# EEZ_DIB_AUX_PS_r3B6.net
KiCad netlist of a schematic drawn in EAGLE
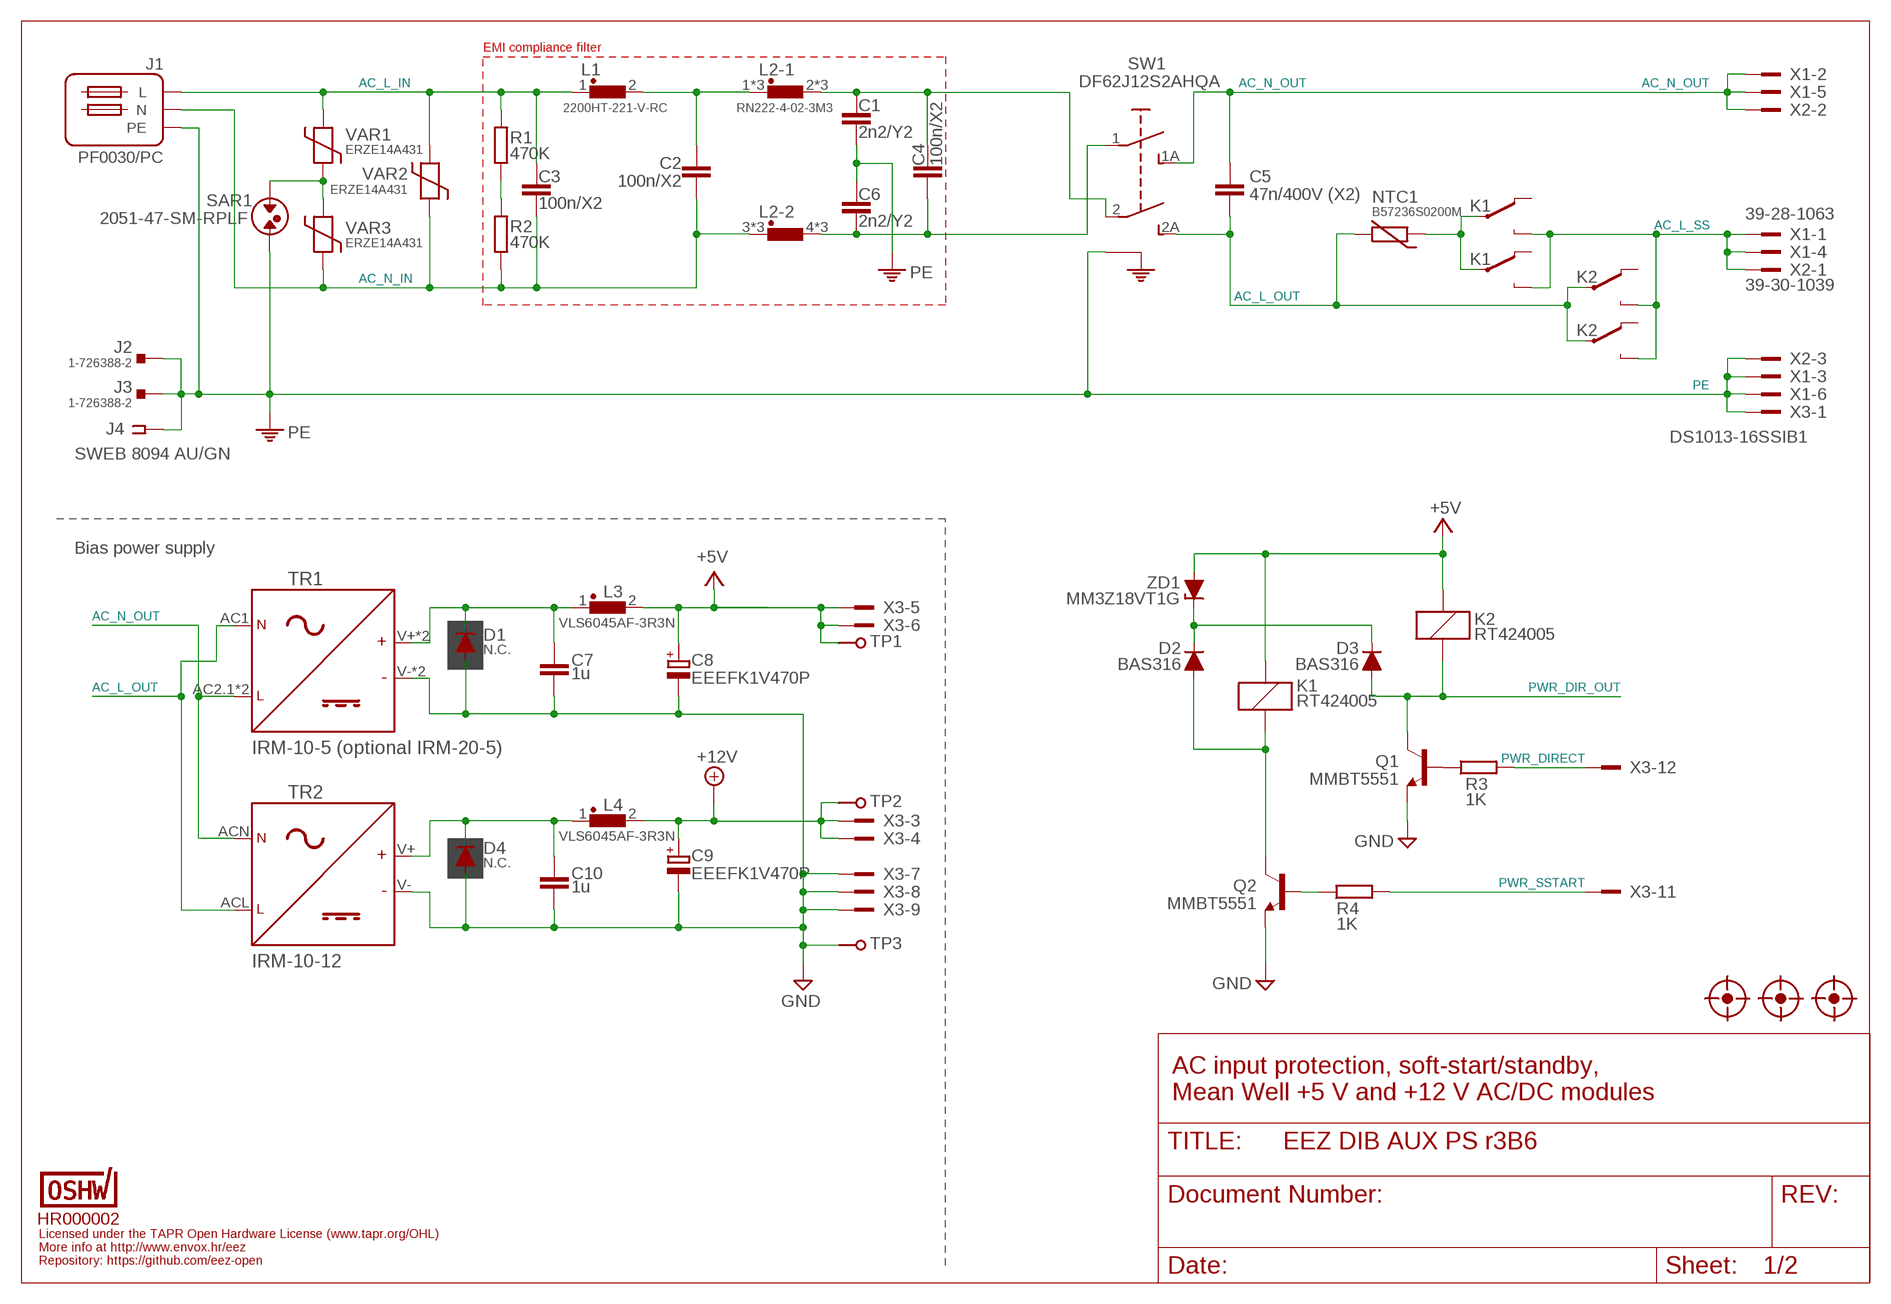
[diagram p0: schematic, sheet 1]
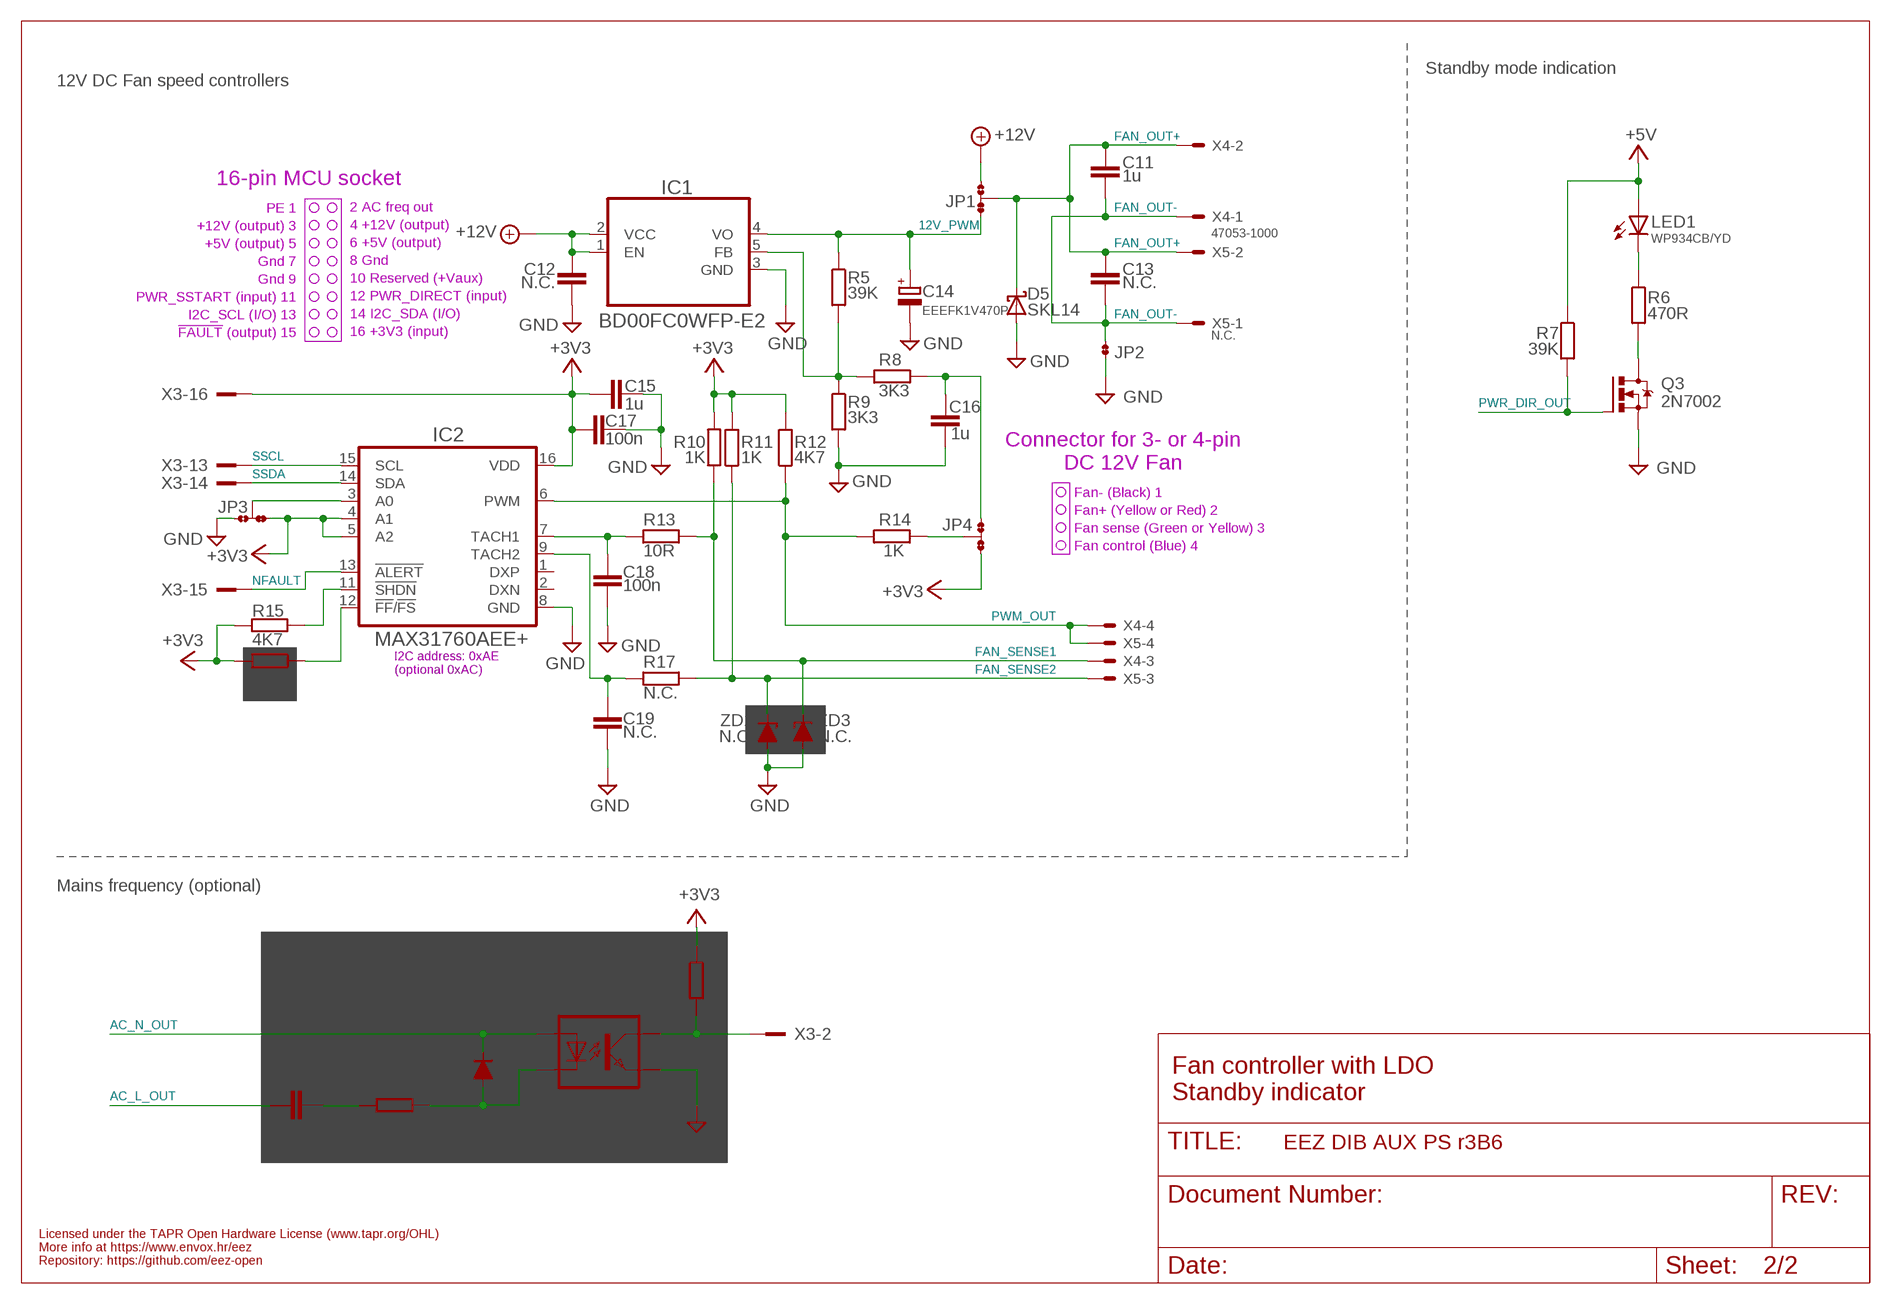
[diagram p1: schematic, sheet 2]

(export (version "E")
  (design (tool "Eeschema 10.0.6"))
  (components
    (comp (ref "C11")
      (value "1u")
      (footprint "eagle-import:C0805")
      (libsource (lib "eagle-import") (part "C-EUC0805"))
    )
    (comp (ref "C12")
      (value "N.C.")
      (footprint "eagle-import:C0805")
      (libsource (lib "eagle-import") (part "C-EUC0805"))
    )
    (comp (ref "C13")
      (value "N.C.")
      (footprint "eagle-import:C0805")
      (libsource (lib "eagle-import") (part "C-EUC0805"))
    )
    (comp (ref "C14")
      (value "EEEFK1V470P")
      (footprint "eagle-import:CAPAE660X610N")
      (libsource (lib "eagle-import") (part "ECAPPANASONIC_H"))
    )
    (comp (ref "C15")
      (value "1u")
      (footprint "eagle-import:C0805")
      (libsource (lib "eagle-import") (part "C-EUC0805"))
    )
    (comp (ref "C16")
      (value "1u")
      (footprint "eagle-import:C0805")
      (libsource (lib "eagle-import") (part "C-EUC0805"))
    )
    (comp (ref "C17")
      (value "100n")
      (footprint "eagle-import:C0603")
      (libsource (lib "eagle-import") (part "C-EUC0603"))
    )
    (comp (ref "C18")
      (value "100n")
      (footprint "eagle-import:C0603")
      (libsource (lib "eagle-import") (part "C-EUC0603"))
    )
    (comp (ref "C19")
      (value "N.C.")
      (footprint "eagle-import:C0603")
      (libsource (lib "eagle-import") (part "C-EUC0603"))
    )
    (comp (ref "C20")
      (value "N.C.")
      (footprint "eagle-import:C102-054X133")
      (libsource (lib "eagle-import") (part "C-EU102-054X133"))
    )
    (comp (ref "D5")
      (value "SKL14")
      (footprint "eagle-import:SOD123")
      (libsource (lib "eagle-import") (part "SCHOTTKYSOD123"))
    )
    (comp (ref "D6")
      (value "N.C.")
      (footprint "eagle-import:SOD323-R")
      (libsource (lib "eagle-import") (part "DIODESOD323R"))
    )
    (comp (ref "IC1")
      (value "BD00FC0WFP-E2")
      (footprint "eagle-import:TO-252-5")
      (libsource (lib "eagle-import") (part "BD00FC0W"))
    )
    (comp (ref "IC2")
      (value "MAX31760AEE+")
      (footprint "eagle-import:DBQ16")
      (libsource (lib "eagle-import") (part "MAX31760AEE+"))
    )
    (comp (ref "JP1")
      (value "JP3-CUT-0805-ROTATED")
      (footprint "eagle-import:JP3-0805-CUT2")
      (libsource (lib "eagle-import") (part "JP3-CUT-0805-ROTATED"))
    )
    (comp (ref "JP2")
      (value "JP2-NOCUT-0805")
      (footprint "eagle-import:JP2-0805-NOCUT")
      (libsource (lib "eagle-import") (part "JP2-NOCUT-0805"))
    )
    (comp (ref "JP3")
      (value "JP3-CUT-0805-ROTATED")
      (footprint "eagle-import:JP3-0805-CUT2")
      (libsource (lib "eagle-import") (part "JP3-CUT-0805-ROTATED"))
    )
    (comp (ref "JP4")
      (value "JP3-CUT-0805-ROTATED")
      (footprint "eagle-import:JP3-0805-CUT2")
      (libsource (lib "eagle-import") (part "JP3-CUT-0805-ROTATED"))
    )
    (comp (ref "LED1")
      (value "WP934CB/YD")
      (footprint "eagle-import:WP934CB_YD")
      (libsource (lib "eagle-import") (part "WP934CB/YD"))
    )
    (comp (ref "OK1")
      (value "N.C.")
      (footprint "eagle-import:SO4")
      (libsource (lib "eagle-import") (part "TLP291"))
    )
    (comp (ref "Q3")
      (value "2N7002")
      (footprint "eagle-import:SOT103P240X110-3N")
      (fields
        (field (name "MPN") "2N7002-7-F")
        (field (name "MPN_1") "2N7002-7-F")
        (field (name "OC_FARNELL") "1713823")
        (field (name "OC_NEWARK") "25R5679")
        (field (name "PACKAGE") "SOT-23-3")
        (field (name "SUPPLIER") "DIODES INC.")
      )
      (libsource (lib "eagle-import") (part "2N7002"))
    )
    (comp (ref "R5")
      (value "39K")
      (footprint "eagle-import:R0805")
      (libsource (lib "eagle-import") (part "R-EU_R0805"))
    )
    (comp (ref "R6")
      (value "470R")
      (footprint "eagle-import:R0805")
      (libsource (lib "eagle-import") (part "R-EU_R0805"))
    )
    (comp (ref "R7")
      (value "39K")
      (footprint "eagle-import:R0805")
      (libsource (lib "eagle-import") (part "R-EU_R0805"))
    )
    (comp (ref "R8")
      (value "3K3")
      (footprint "eagle-import:R0805")
      (libsource (lib "eagle-import") (part "R-EU_R0805"))
    )
    (comp (ref "R9")
      (value "3K3")
      (footprint "eagle-import:R0805")
      (libsource (lib "eagle-import") (part "R-EU_R0805"))
    )
    (comp (ref "R10")
      (value "1K")
      (footprint "eagle-import:R0805")
      (libsource (lib "eagle-import") (part "R-EU_R0805"))
    )
    (comp (ref "R11")
      (value "1K")
      (footprint "eagle-import:R0805")
      (libsource (lib "eagle-import") (part "R-EU_R0805"))
    )
    (comp (ref "R12")
      (value "4K7")
      (footprint "eagle-import:R0805")
      (libsource (lib "eagle-import") (part "R-EU_R0805"))
    )
    (comp (ref "R13")
      (value "10R")
      (footprint "eagle-import:R0805")
      (libsource (lib "eagle-import") (part "R-EU_R0805"))
    )
    (comp (ref "R14")
      (value "1K")
      (footprint "eagle-import:R0805")
      (libsource (lib "eagle-import") (part "R-EU_R0805"))
    )
    (comp (ref "R15")
      (value "4K7")
      (footprint "eagle-import:R0805")
      (libsource (lib "eagle-import") (part "R-EU_R0805"))
    )
    (comp (ref "R16")
      (value "N.C.")
      (footprint "eagle-import:R0805")
      (libsource (lib "eagle-import") (part "R-EU_R0805"))
    )
    (comp (ref "R17")
      (value "N.C.")
      (footprint "eagle-import:R0805")
      (libsource (lib "eagle-import") (part "R-EU_R0805"))
    )
    (comp (ref "R18")
      (value "N.C.")
      (footprint "eagle-import:R0805")
      (libsource (lib "eagle-import") (part "R-EU_R0805"))
    )
    (comp (ref "R19")
      (value "N.C.")
      (footprint "eagle-import:R0805")
      (libsource (lib "eagle-import") (part "R-EU_R0805"))
    )
    (comp (ref "X3")
      (value "DS1013-16SSIB1")
      (footprint "eagle-import:IDC-16PIN")
      (libsource (lib "eagle-import") (part "IDC-16PIN"))
    )
    (comp (ref "X4")
      (value "47053-1000")
      (footprint "eagle-import:47053-1000")
      (libsource (lib "eagle-import") (part "47053-1000"))
    )
    (comp (ref "X5")
      (value "N.C.")
      (footprint "eagle-import:47053-1000")
      (libsource (lib "eagle-import") (part "47053-1000"))
    )
    (comp (ref "ZD2")
      (value "N.C.")
      (footprint "eagle-import:SOD123")
      (libsource (lib "eagle-import") (part "ZENER-DIODESOD123"))
    )
    (comp (ref "ZD3")
      (value "N.C.")
      (footprint "eagle-import:SOD123")
      (libsource (lib "eagle-import") (part "ZENER-DIODESOD123"))
    )
    (comp (ref "C1")
      (value "2n2/Y2")
      (footprint "eagle-import:C075-042X103")
      (libsource (lib "eagle-import") (part "C-EU075-042X103"))
    )
    (comp (ref "C2")
      (value "100n/X2")
      (footprint "eagle-import:C150-054X183")
      (libsource (lib "eagle-import") (part "C-EU150-054X183"))
    )
    (comp (ref "C3")
      (value "100n/X2")
      (footprint "eagle-import:C150-054X183")
      (libsource (lib "eagle-import") (part "C-EU150-054X183"))
    )
    (comp (ref "C4")
      (value "100n/X2")
      (footprint "eagle-import:C150-054X183")
      (libsource (lib "eagle-import") (part "C-EU150-054X183"))
    )
    (comp (ref "C5")
      (value "47n/400V (X2)")
      (footprint "eagle-import:C102-054X133")
      (libsource (lib "eagle-import") (part "C-EU102-054X133"))
    )
    (comp (ref "C6")
      (value "2n2/Y2")
      (footprint "eagle-import:C075-042X103")
      (libsource (lib "eagle-import") (part "C-EU075-042X103"))
    )
    (comp (ref "C7")
      (value "1u")
      (footprint "eagle-import:C0805")
      (libsource (lib "eagle-import") (part "C-EUC0805"))
    )
    (comp (ref "C8")
      (value "EEEFK1V470P")
      (footprint "eagle-import:CAPAE660X610N")
      (libsource (lib "eagle-import") (part "ECAPPANASONIC_H"))
    )
    (comp (ref "C9")
      (value "EEEFK1V470P")
      (footprint "eagle-import:CAPAE660X610N")
      (libsource (lib "eagle-import") (part "ECAPPANASONIC_H"))
    )
    (comp (ref "C10")
      (value "1u")
      (footprint "eagle-import:C0805")
      (libsource (lib "eagle-import") (part "C-EUC0805"))
    )
    (comp (ref "D1")
      (value "N.C.")
      (footprint "eagle-import:DO214AA")
      (libsource (lib "eagle-import") (part "MyLib6_DIODEDO214AA"))
    )
    (comp (ref "D2")
      (value "BAS316")
      (footprint "eagle-import:SOD323-R")
      (libsource (lib "eagle-import") (part "DIODESOD323R"))
    )
    (comp (ref "D3")
      (value "BAS316")
      (footprint "eagle-import:SOD323-R")
      (libsource (lib "eagle-import") (part "DIODESOD323R"))
    )
    (comp (ref "D4")
      (value "N.C.")
      (footprint "eagle-import:DO214AA")
      (libsource (lib "eagle-import") (part "MyLib6_DIODEDO214AA"))
    )
    (comp (ref "FM1")
      (value "FIDUCIAL")
      (footprint "eagle-import:FIDUCIAL")
      (libsource (lib "eagle-import") (part "FIDUCIAL"))
    )
    (comp (ref "FM2")
      (value "FIDUCIAL")
      (footprint "eagle-import:FIDUCIAL")
      (libsource (lib "eagle-import") (part "FIDUCIAL"))
    )
    (comp (ref "FM3")
      (value "FIDUCIAL")
      (footprint "eagle-import:FIDUCIAL")
      (libsource (lib "eagle-import") (part "FIDUCIAL"))
    )
    (comp (ref "J1")
      (value "PF0030/PC")
      (footprint "eagle-import:PF0030_PC")
      (libsource (lib "eagle-import") (part "PF0030/PC"))
    )
    (comp (ref "J2")
      (value "1-726388-2")
      (footprint "eagle-import:PCB_TAB-4.8MM")
      (libsource (lib "eagle-import") (part "PCB_TAB4.8MM"))
    )
    (comp (ref "J3")
      (value "1-726388-2")
      (footprint "eagle-import:PCB_TAB-4.8MM")
      (libsource (lib "eagle-import") (part "PCB_TAB4.8MM"))
    )
    (comp (ref "J4")
      (value "SWEB 8094 AU/GN")
      (footprint "eagle-import:S16N-PC")
      (libsource (lib "eagle-import") (part "BINDING_POSTCLIFF"))
    )
    (comp (ref "K1")
      (value "RT424005")
      (footprint "eagle-import:RT-C_016A5_ROUND")
      (libsource (lib "eagle-import") (part "RELAY_RT314012-2"))
    )
    (comp (ref "K2")
      (value "RT424005")
      (footprint "eagle-import:RT-C_016A5_ROUND")
      (libsource (lib "eagle-import") (part "RELAY_RT314012-2"))
    )
    (comp (ref "L1")
      (value "2200HT-221-V-RC")
      (footprint "eagle-import:BOURNS_2200")
      (libsource (lib "eagle-import") (part "BOURNS_2200"))
    )
    (comp (ref "L2")
      (value "RN222-4-02-3M3")
      (footprint "eagle-import:BOURNS_7100_COMBO")
      (libsource (lib "eagle-import") (part "BOURNS_7100-COMBO"))
    )
    (comp (ref "L3")
      (value "VLS6045AF-3R3N")
      (footprint "eagle-import:COILCRAFT_HPI0630")
      (libsource (lib "eagle-import") (part "COILCRAFT_HPI0630"))
    )
    (comp (ref "L4")
      (value "VLS6045AF-3R3N")
      (footprint "eagle-import:COILCRAFT_HPI0630")
      (libsource (lib "eagle-import") (part "COILCRAFT_HPI0630"))
    )
    (comp (ref "LABEL1")
      (value "HR000002")
      (footprint "eagle-import:CERT-SMALL-SILK")
      (libsource (lib "eagle-import") (part "OSHWA-CERT-SMALL"))
    )
    (comp (ref "NTC1")
      (value "B57236S0200M")
      (footprint "eagle-import:NTC_11.5X6_RM5")
      (libsource (lib "eagle-import") (part "NTC11.5X6"))
    )
    (comp (ref "Q1")
      (value "MMBT5551")
      (footprint "eagle-import:SOT23-BEC")
      (libsource (lib "eagle-import") (part "-NPN-SOT23-BECMMBT5551LT1"))
    )
    (comp (ref "Q2")
      (value "MMBT5551")
      (footprint "eagle-import:SOT23-BEC")
      (libsource (lib "eagle-import") (part "-NPN-SOT23-BECMMBT5551LT1"))
    )
    (comp (ref "R1")
      (value "470K")
      (footprint "eagle-import:R1206")
      (libsource (lib "eagle-import") (part "R-EU_R1206"))
    )
    (comp (ref "R2")
      (value "470K")
      (footprint "eagle-import:R1206")
      (libsource (lib "eagle-import") (part "R-EU_R1206"))
    )
    (comp (ref "R3")
      (value "1K")
      (footprint "eagle-import:R0805")
      (libsource (lib "eagle-import") (part "R-EU_R0805"))
    )
    (comp (ref "R4")
      (value "1K")
      (footprint "eagle-import:R0805")
      (libsource (lib "eagle-import") (part "R-EU_R0805"))
    )
    (comp (ref "SAR1")
      (value "2051-47-SM-RPLF")
      (footprint "eagle-import:SAR_4.5MM")
      (libsource (lib "eagle-import") (part "SAR-SG"))
    )
    (comp (ref "SW1")
      (value "DF62J12S2AHQA")
      (footprint "eagle-import:DF62J12S2")
      (libsource (lib "eagle-import") (part "DF62J12S2AHQA"))
    )
    (comp (ref "TP1")
      (value "PCB_TEST_TABSHIELD")
      (footprint "eagle-import:PCB_SHIELD_TAB")
      (libsource (lib "eagle-import") (part "PCB_TEST_TABSHIELD"))
    )
    (comp (ref "TP2")
      (value "PCB_TEST_TABSHIELD")
      (footprint "eagle-import:PCB_SHIELD_TAB")
      (libsource (lib "eagle-import") (part "PCB_TEST_TABSHIELD"))
    )
    (comp (ref "TP3")
      (value "PCB_TEST_TABSHIELD")
      (footprint "eagle-import:PCB_SHIELD_TAB")
      (libsource (lib "eagle-import") (part "PCB_TEST_TABSHIELD"))
    )
    (comp (ref "TR1")
      (value "IRM-10-5 (optional IRM-20-5)")
      (footprint "eagle-import:IRM-10_20_COMBO")
      (libsource (lib "eagle-import") (part "AC_DC_ADAPTERIRM10/20"))
    )
    (comp (ref "TR2")
      (value "IRM-10-12")
      (footprint "eagle-import:IRM-10")
      (libsource (lib "eagle-import") (part "AC_DC_ADAPTERIRM10"))
    )
    (comp (ref "VAR1")
      (value "ERZE14A431")
      (footprint "eagle-import:VARISTOR_16MM")
      (libsource (lib "eagle-import") (part "VARISTOR-16"))
    )
    (comp (ref "VAR2")
      (value "ERZE14A431")
      (footprint "eagle-import:VARISTOR_16MM")
      (libsource (lib "eagle-import") (part "VARISTOR-16"))
    )
    (comp (ref "VAR3")
      (value "ERZE14A431")
      (footprint "eagle-import:VARISTOR_16MM")
      (libsource (lib "eagle-import") (part "VARISTOR-16"))
    )
    (comp (ref "X1")
      (value "39-28-1063")
      (footprint "eagle-import:MINIFIT_5566-06A_CRE")
      (libsource (lib "eagle-import") (part "MINIFIT_5566-06A-CRE"))
    )
    (comp (ref "X2")
      (value "39-30-1039")
      (footprint "eagle-import:MINIFIT_39301039_CRE")
      (libsource (lib "eagle-import") (part "MINIFIT_39301039-CREEPAGE"))
    )
    (comp (ref "ZD1")
      (value "MM3Z18VT1G")
      (footprint "eagle-import:SOD323-R")
      (libsource (lib "eagle-import") (part "ZENER-DIODESOD323R"))
    )
  )
  (nets
    (net (code "1") (name "+3V3") (class "Default")
      (node (ref "C15") (pin "2") (pinfunction "2_2") (pintype "passive"))
      (node (ref "C17") (pin "2") (pinfunction "2_2") (pintype "passive"))
      (node (ref "IC2") (pin "16") (pinfunction "VDD_16") (pintype "power_in"))
      (node (ref "IC2") (pin "4") (pinfunction "A1_4") (pintype "input"))
      (node (ref "IC2") (pin "5") (pinfunction "A2_5") (pintype "input"))
      (node (ref "JP3") (pin "NC") (pinfunction "NC_NC") (pintype "passive"))
      (node (ref "JP4") (pin "NO") (pinfunction "NO_NO") (pintype "passive"))
      (node (ref "R10") (pin "2") (pinfunction "2_2") (pintype "passive"))
      (node (ref "R11") (pin "2") (pinfunction "2_2") (pintype "passive"))
      (node (ref "R12") (pin "2") (pinfunction "2_2") (pintype "passive"))
      (node (ref "R15") (pin "2") (pinfunction "2_2") (pintype "passive"))
      (node (ref "R16") (pin "2") (pinfunction "2_2") (pintype "passive"))
      (node (ref "R18") (pin "1") (pinfunction "1_1") (pintype "passive"))
      (node (ref "X3") (pin "16") (pinfunction "1_16") (pintype "passive"))
    )
    (net (code "2") (name "+5V") (class "Default")
      (node (ref "C8") (pin "1") (pinfunction "+_1") (pintype "passive"))
      (node (ref "K1") (pin "A2") (pinfunction "C1_A2") (pintype "passive"))
      (node (ref "K2") (pin "A1") (pinfunction "C2_A1") (pintype "passive"))
      (node (ref "L3") (pin "2") (pinfunction "2_2") (pintype "passive"))
      (node (ref "LED1") (pin "A") (pinfunction "A_A") (pintype "passive"))
      (node (ref "R7") (pin "1") (pinfunction "1_1") (pintype "passive"))
      (node (ref "TP1") (pin "1") (pinfunction "P$1_1") (pintype "bidirectional"))
      (node (ref "X3") (pin "5") (pinfunction "1_5") (pintype "passive"))
      (node (ref "X3") (pin "6") (pinfunction "1_6") (pintype "passive"))
      (node (ref "ZD1") (pin "A") (pinfunction "A_A") (pintype "passive"))
    )
    (net (code "3") (name "+12V") (class "Default")
      (node (ref "C12") (pin "1") (pinfunction "1_1") (pintype "passive"))
      (node (ref "C9") (pin "1") (pinfunction "+_1") (pintype "passive"))
      (node (ref "IC1") (pin "1") (pinfunction "EN_1") (pintype "passive"))
      (node (ref "IC1") (pin "2") (pinfunction "VCC_2") (pintype "passive"))
      (node (ref "JP1") (pin "NO") (pinfunction "NO_NO") (pintype "passive"))
      (node (ref "L4") (pin "2") (pinfunction "2_2") (pintype "passive"))
      (node (ref "TP2") (pin "1") (pinfunction "P$1_1") (pintype "bidirectional"))
      (node (ref "X3") (pin "3") (pinfunction "1_3") (pintype "passive"))
      (node (ref "X3") (pin "4") (pinfunction "1_4") (pintype "passive"))
    )
    (net (code "4") (name "12V_PWM") (class "Default")
      (node (ref "C14") (pin "1") (pinfunction "+_1") (pintype "passive"))
      (node (ref "IC1") (pin "4") (pinfunction "VO_4") (pintype "output"))
      (node (ref "JP1") (pin "NC") (pinfunction "NC_NC") (pintype "passive"))
      (node (ref "R5") (pin "1") (pinfunction "1_1") (pintype "passive"))
    )
    (net (code "5") (name "AC_L_IN") (class "Default")
      (node (ref "C3") (pin "1") (pinfunction "1_1") (pintype "passive"))
      (node (ref "J1") (pin "L") (pinfunction "L_L") (pintype "bidirectional"))
      (node (ref "L1") (pin "1") (pinfunction "1_1") (pintype "passive"))
      (node (ref "R1") (pin "2") (pinfunction "2_2") (pintype "passive"))
      (node (ref "VAR1") (pin "2") (pinfunction "P$2_2") (pintype "bidirectional"))
      (node (ref "VAR2") (pin "1") (pinfunction "P$1_1") (pintype "bidirectional"))
    )
    (net (code "6") (name "AC_L_OUT") (class "Default")
      (node (ref "C20") (pin "1") (pinfunction "1_1") (pintype "passive"))
      (node (ref "C5") (pin "2") (pinfunction "2_2") (pintype "passive"))
      (node (ref "K2") (pin "11A") (pinfunction "P_11A") (pintype "passive"))
      (node (ref "K2") (pin "11B") (pinfunction "P_11B") (pintype "passive"))
      (node (ref "NTC1") (pin "1") (pinfunction "P$1_1") (pintype "bidirectional"))
      (node (ref "SW1") (pin "2A") (pinfunction "S1_2A") (pintype "passive"))
      (node (ref "TR1") (pin "AC1") (pinfunction "AC/N_AC1") (pintype "input"))
      (node (ref "TR2") (pin "ACL") (pinfunction "AC/L_ACL") (pintype "input"))
    )
    (net (code "7") (name "AC_L_SS") (class "Default")
      (node (ref "K1") (pin "14A") (pinfunction "O_14A") (pintype "passive"))
      (node (ref "K1") (pin "14B") (pinfunction "O_14B") (pintype "passive"))
      (node (ref "K2") (pin "14A") (pinfunction "O_14A") (pintype "passive"))
      (node (ref "K2") (pin "14B") (pinfunction "O_14B") (pintype "passive"))
      (node (ref "X1") (pin "1") (pinfunction "1_1") (pintype "passive"))
      (node (ref "X1") (pin "4") (pinfunction "1_4") (pintype "passive"))
      (node (ref "X2") (pin "1") (pinfunction "1_1") (pintype "passive"))
    )
    (net (code "8") (name "AC_N_IN") (class "Default")
      (node (ref "C2") (pin "2") (pinfunction "2_2") (pintype "passive"))
      (node (ref "C3") (pin "2") (pinfunction "2_2") (pintype "passive"))
      (node (ref "J1") (pin "N") (pinfunction "N_N") (pintype "bidirectional"))
      (node (ref "L2") (pin "3") (pinfunction "1_3") (pintype "passive"))
      (node (ref "L2") (pin "3A") (pinfunction "1_3A") (pintype "passive"))
      (node (ref "L2") (pin "3B") (pinfunction "1_3B") (pintype "passive"))
      (node (ref "R2") (pin "1") (pinfunction "1_1") (pintype "passive"))
      (node (ref "VAR2") (pin "2") (pinfunction "P$2_2") (pintype "bidirectional"))
      (node (ref "VAR3") (pin "1") (pinfunction "P$1_1") (pintype "bidirectional"))
    )
    (net (code "9") (name "AC_N_OUT") (class "Default")
      (node (ref "C5") (pin "1") (pinfunction "1_1") (pintype "passive"))
      (node (ref "D6") (pin "C") (pinfunction "C_C") (pintype "passive"))
      (node (ref "OK1") (pin "1") (pinfunction "A_1") (pintype "passive"))
      (node (ref "SW1") (pin "1A") (pinfunction "S_1A") (pintype "passive"))
      (node (ref "TR1") (pin "AC2.1") (pinfunction "AC/L_AC2.1") (pintype "input"))
      (node (ref "TR1") (pin "AC2.2") (pinfunction "AC/L_AC2.2") (pintype "input"))
      (node (ref "TR2") (pin "ACN") (pinfunction "AC/N_ACN") (pintype "input"))
      (node (ref "X1") (pin "2") (pinfunction "1_2") (pintype "passive"))
      (node (ref "X1") (pin "5") (pinfunction "1_5") (pintype "passive"))
      (node (ref "X2") (pin "2") (pinfunction "1_2") (pintype "passive"))
    )
    (net (code "10") (name "FAN_OUT+") (class "Default")
      (node (ref "C11") (pin "1") (pinfunction "1_1") (pintype "passive"))
      (node (ref "C13") (pin "1") (pinfunction "1_1") (pintype "passive"))
      (node (ref "D5") (pin "C") (pinfunction "C_C") (pintype "passive"))
      (node (ref "JP1") (pin "COM") (pinfunction "COM_COM") (pintype "passive"))
      (node (ref "X4") (pin "2") (pinfunction "S_2") (pintype "passive"))
      (node (ref "X5") (pin "2") (pinfunction "S_2") (pintype "passive"))
    )
    (net (code "11") (name "FAN_OUT-") (class "Default")
      (node (ref "C11") (pin "2") (pinfunction "2_2") (pintype "passive"))
      (node (ref "C13") (pin "2") (pinfunction "2_2") (pintype "passive"))
      (node (ref "JP2") (pin "2") (pinfunction "2_2") (pintype "passive"))
      (node (ref "X4") (pin "1") (pinfunction "S_1") (pintype "passive"))
      (node (ref "X5") (pin "1") (pinfunction "S_1") (pintype "passive"))
    )
    (net (code "12") (name "FAN_SENSE1") (class "Default")
      (node (ref "R10") (pin "1") (pinfunction "1_1") (pintype "passive"))
      (node (ref "R13") (pin "2") (pinfunction "2_2") (pintype "passive"))
      (node (ref "X4") (pin "3") (pinfunction "S_3") (pintype "passive"))
      (node (ref "ZD3") (pin "C") (pinfunction "C_C") (pintype "passive"))
    )
    (net (code "13") (name "FAN_SENSE2") (class "Default")
      (node (ref "R11") (pin "1") (pinfunction "1_1") (pintype "passive"))
      (node (ref "R17") (pin "2") (pinfunction "2_2") (pintype "passive"))
      (node (ref "X5") (pin "3") (pinfunction "S_3") (pintype "passive"))
      (node (ref "ZD2") (pin "C") (pinfunction "C_C") (pintype "passive"))
    )
    (net (code "14") (name "GND") (class "Default")
      (node (ref "C10") (pin "2") (pinfunction "2_2") (pintype "passive"))
      (node (ref "C12") (pin "2") (pinfunction "2_2") (pintype "passive"))
      (node (ref "C14") (pin "2") (pinfunction "-_2") (pintype "passive"))
      (node (ref "C15") (pin "1") (pinfunction "1_1") (pintype "passive"))
      (node (ref "C16") (pin "2") (pinfunction "2_2") (pintype "passive"))
      (node (ref "C17") (pin "1") (pinfunction "1_1") (pintype "passive"))
      (node (ref "C18") (pin "2") (pinfunction "2_2") (pintype "passive"))
      (node (ref "C19") (pin "2") (pinfunction "2_2") (pintype "passive"))
      (node (ref "C7") (pin "2") (pinfunction "2_2") (pintype "passive"))
      (node (ref "C8") (pin "2") (pinfunction "-_2") (pintype "passive"))
      (node (ref "C9") (pin "2") (pinfunction "-_2") (pintype "passive"))
      (node (ref "D1") (pin "A") (pinfunction "A_A") (pintype "passive"))
      (node (ref "D4") (pin "A") (pinfunction "A_A") (pintype "passive"))
      (node (ref "D5") (pin "A") (pinfunction "A_A") (pintype "passive"))
      (node (ref "IC1") (pin "3") (pinfunction "GND_3") (pintype "passive"))
      (node (ref "IC2") (pin "8") (pinfunction "GND_8") (pintype "power_in"))
      (node (ref "JP2") (pin "1") (pinfunction "1_1") (pintype "passive"))
      (node (ref "JP3") (pin "NO") (pinfunction "NO_NO") (pintype "passive"))
      (node (ref "OK1") (pin "3") (pinfunction "EMIT_3") (pintype "passive"))
      (node (ref "Q1") (pin "E") (pinfunction "E_E") (pintype "passive"))
      (node (ref "Q2") (pin "E") (pinfunction "E_E") (pintype "passive"))
      (node (ref "Q3") (pin "2") (pinfunction "S_2") (pintype "passive"))
      (node (ref "R9") (pin "2") (pinfunction "2_2") (pintype "passive"))
      (node (ref "TP3") (pin "1") (pinfunction "P$1_1") (pintype "bidirectional"))
      (node (ref "TR1") (pin "V-") (pinfunction "-_V-") (pintype "passive"))
      (node (ref "TR1") (pin "V-1") (pinfunction "-_V-1") (pintype "passive"))
      (node (ref "TR2") (pin "V-") (pinfunction "-_V-") (pintype "passive"))
      (node (ref "X3") (pin "7") (pinfunction "1_7") (pintype "passive"))
      (node (ref "X3") (pin "8") (pinfunction "1_8") (pintype "passive"))
      (node (ref "X3") (pin "9") (pinfunction "1_9") (pintype "passive"))
      (node (ref "ZD2") (pin "A") (pinfunction "A_A") (pintype "passive"))
      (node (ref "ZD3") (pin "A") (pinfunction "A_A") (pintype "passive"))
    )
    (net (code "15") (name "NFAULT") (class "Default")
      (node (ref "IC2") (pin "13") (pinfunction "~{ALERT}_13") (pintype "output"))
      (node (ref "X3") (pin "15") (pinfunction "1_15") (pintype "passive"))
    )
    (net (code "16") (name "Net-(C2-Pad1)") (class "Default")
      (node (ref "C2") (pin "1") (pinfunction "1_1") (pintype "passive"))
      (node (ref "L1") (pin "2") (pinfunction "2_2") (pintype "passive"))
      (node (ref "L2") (pin "1") (pinfunction "1_1") (pintype "passive"))
      (node (ref "L2") (pin "1A") (pinfunction "1_1A") (pintype "passive"))
      (node (ref "L2") (pin "1B") (pinfunction "1_1B") (pintype "passive"))
    )
    (net (code "17") (name "Net-(C7-Pad1)") (class "Default")
      (node (ref "C7") (pin "1") (pinfunction "1_1") (pintype "passive"))
      (node (ref "D1") (pin "C") (pinfunction "C_C") (pintype "passive"))
      (node (ref "L3") (pin "1") (pinfunction "1_1") (pintype "passive"))
      (node (ref "TR1") (pin "V+") (pinfunction "+_V+") (pintype "passive"))
      (node (ref "TR1") (pin "V+1") (pinfunction "+_V+1") (pintype "passive"))
    )
    (net (code "18") (name "Net-(C16-Pad1)") (class "Default")
      (node (ref "C16") (pin "1") (pinfunction "1_1") (pintype "passive"))
      (node (ref "JP4") (pin "NC") (pinfunction "NC_NC") (pintype "passive"))
      (node (ref "R8") (pin "2") (pinfunction "2_2") (pintype "passive"))
    )
    (net (code "19") (name "Net-(C20-Pad2)") (class "Default")
      (node (ref "C20") (pin "2") (pinfunction "2_2") (pintype "passive"))
      (node (ref "R19") (pin "1") (pinfunction "1_1") (pintype "passive"))
    )
    (net (code "20") (name "Net-(D2-PadC)") (class "Default")
      (node (ref "D2") (pin "C") (pinfunction "C_C") (pintype "passive"))
      (node (ref "D3") (pin "C") (pinfunction "C_C") (pintype "passive"))
      (node (ref "ZD1") (pin "C") (pinfunction "C_C") (pintype "passive"))
    )
    (net (code "21") (name "Net-(IC1-FB)") (class "Default")
      (node (ref "IC1") (pin "5") (pinfunction "FB_5") (pintype "passive"))
      (node (ref "R5") (pin "2") (pinfunction "2_2") (pintype "passive"))
      (node (ref "R8") (pin "1") (pinfunction "1_1") (pintype "passive"))
      (node (ref "R9") (pin "1") (pinfunction "1_1") (pintype "passive"))
    )
    (net (code "22") (name "Net-(IC2-A0)") (class "Default")
      (node (ref "IC2") (pin "3") (pinfunction "A0_3") (pintype "input"))
      (node (ref "JP3") (pin "COM") (pinfunction "COM_COM") (pintype "passive"))
    )
    (net (code "23") (name "Net-(IC2-TACH1)") (class "Default")
      (node (ref "C18") (pin "1") (pinfunction "1_1") (pintype "passive"))
      (node (ref "IC2") (pin "7") (pinfunction "TACH1_7") (pintype "input"))
      (node (ref "R13") (pin "1") (pinfunction "1_1") (pintype "passive"))
    )
    (net (code "24") (name "Net-(IC2-TACH2)") (class "Default")
      (node (ref "C19") (pin "1") (pinfunction "1_1") (pintype "passive"))
      (node (ref "IC2") (pin "9") (pinfunction "TACH2_9") (pintype "input"))
      (node (ref "R17") (pin "1") (pinfunction "1_1") (pintype "passive"))
    )
    (net (code "25") (name "Net-(IC2-~{FF}{slash}~{FS})") (class "Default")
      (node (ref "IC2") (pin "12") (pinfunction "~{FF}/~{FS}_12") (pintype "bidirectional"))
      (node (ref "R16") (pin "1") (pinfunction "1_1") (pintype "passive"))
    )
    (net (code "26") (name "Net-(IC2-~{SHDN})") (class "Default")
      (node (ref "IC2") (pin "11") (pinfunction "~{SHDN}_11") (pintype "output"))
      (node (ref "R15") (pin "1") (pinfunction "1_1") (pintype "passive"))
    )
    (net (code "27") (name "Net-(JP4-PadCOM)") (class "Default")
      (node (ref "JP4") (pin "COM") (pinfunction "COM_COM") (pintype "passive"))
      (node (ref "R14") (pin "1") (pinfunction "1_1") (pintype "passive"))
    )
    (net (code "28") (name "Net-(K1A-P)") (class "Default")
      (node (ref "K1") (pin "11A") (pinfunction "P_11A") (pintype "passive"))
      (node (ref "K1") (pin "11B") (pinfunction "P_11B") (pintype "passive"))
      (node (ref "NTC1") (pin "2") (pinfunction "P$2_2") (pintype "bidirectional"))
    )
    (net (code "29") (name "Net-(K1C-C2)") (class "Default")
      (node (ref "D2") (pin "A") (pinfunction "A_A") (pintype "passive"))
      (node (ref "K1") (pin "A1") (pinfunction "C2_A1") (pintype "passive"))
      (node (ref "Q2") (pin "C") (pinfunction "C_C") (pintype "passive"))
    )
    (net (code "30") (name "Net-(LED1-PadC)") (class "Default")
      (node (ref "LED1") (pin "C") (pinfunction "C_C") (pintype "passive"))
      (node (ref "R6") (pin "1") (pinfunction "1_1") (pintype "passive"))
    )
    (net (code "31") (name "Net-(OK1-C)") (class "Default")
      (node (ref "D6") (pin "A") (pinfunction "A_A") (pintype "passive"))
      (node (ref "OK1") (pin "2") (pinfunction "C_2") (pintype "passive"))
      (node (ref "R19") (pin "2") (pinfunction "2_2") (pintype "passive"))
    )
    (net (code "32") (name "Net-(OK1-COL)") (class "Default")
      (node (ref "OK1") (pin "4") (pinfunction "COL_4") (pintype "passive"))
      (node (ref "R18") (pin "2") (pinfunction "2_2") (pintype "passive"))
      (node (ref "X3") (pin "2") (pinfunction "1_2") (pintype "passive"))
    )
    (net (code "33") (name "Net-(Q1-PadB)") (class "Default")
      (node (ref "Q1") (pin "B") (pinfunction "B_B") (pintype "passive"))
      (node (ref "R3") (pin "1") (pinfunction "1_1") (pintype "passive"))
    )
    (net (code "34") (name "Net-(Q2-PadB)") (class "Default")
      (node (ref "Q2") (pin "B") (pinfunction "B_B") (pintype "passive"))
      (node (ref "R4") (pin "1") (pinfunction "1_1") (pintype "passive"))
    )
    (net (code "35") (name "Net-(Q3-D)") (class "Default")
      (node (ref "Q3") (pin "3") (pinfunction "D_3") (pintype "passive"))
      (node (ref "R6") (pin "2") (pinfunction "2_2") (pintype "passive"))
    )
    (net (code "36") (name "Net-(R1-Pad1)") (class "Default")
      (node (ref "R1") (pin "1") (pinfunction "1_1") (pintype "passive"))
      (node (ref "R2") (pin "2") (pinfunction "2_2") (pintype "passive"))
    )
    (net (code "37") (name "Net-(SAR1-P$1)") (class "Default")
      (node (ref "SAR1") (pin "1") (pinfunction "P$1_1") (pintype "bidirectional"))
      (node (ref "VAR1") (pin "1") (pinfunction "P$1_1") (pintype "bidirectional"))
      (node (ref "VAR3") (pin "2") (pinfunction "P$2_2") (pintype "bidirectional"))
    )
    (net (code "38") (name "Net-(SW1-P)") (class "Default")
      (node (ref "C4") (pin "1") (pinfunction "1_1") (pintype "passive"))
      (node (ref "C6") (pin "2") (pinfunction "2_2") (pintype "passive"))
      (node (ref "L2") (pin "4") (pinfunction "2_4") (pintype "passive"))
      (node (ref "L2") (pin "4A") (pinfunction "2_4A") (pintype "passive"))
      (node (ref "L2") (pin "4B") (pinfunction "2_4B") (pintype "passive"))
      (node (ref "SW1") (pin "1") (pinfunction "P_1") (pintype "passive"))
    )
    (net (code "39") (name "Net-(SW1-P1)") (class "Default")
      (node (ref "C1") (pin "1") (pinfunction "1_1") (pintype "passive"))
      (node (ref "C4") (pin "2") (pinfunction "2_2") (pintype "passive"))
      (node (ref "L2") (pin "2") (pinfunction "2_2") (pintype "passive"))
      (node (ref "L2") (pin "2A") (pinfunction "2_2A") (pintype "passive"))
      (node (ref "L2") (pin "2B") (pinfunction "2_2B") (pintype "passive"))
      (node (ref "SW1") (pin "2") (pinfunction "P1_2") (pintype "passive"))
    )
    (net (code "40") (name "Net-(TR2-+)") (class "Default")
      (node (ref "C10") (pin "1") (pinfunction "1_1") (pintype "passive"))
      (node (ref "D4") (pin "C") (pinfunction "C_C") (pintype "passive"))
      (node (ref "L4") (pin "1") (pinfunction "1_1") (pintype "passive"))
      (node (ref "TR2") (pin "V+") (pinfunction "+_V+") (pintype "passive"))
    )
    (net (code "41") (name "PE") (class "Default")
      (node (ref "C1") (pin "2") (pinfunction "2_2") (pintype "passive"))
      (node (ref "C6") (pin "1") (pinfunction "1_1") (pintype "passive"))
      (node (ref "J1") (pin "PE") (pinfunction "PE_PE") (pintype "bidirectional"))
      (node (ref "J2") (pin "1") (pinfunction "P$1_1") (pintype "bidirectional"))
      (node (ref "J2") (pin "2") (pinfunction "P$1_2") (pintype "bidirectional"))
      (node (ref "J3") (pin "1") (pinfunction "P$1_1") (pintype "bidirectional"))
      (node (ref "J3") (pin "2") (pinfunction "P$1_2") (pintype "bidirectional"))
      (node (ref "J4") (pin "1") (pinfunction "1_1") (pintype "passive"))
      (node (ref "J4") (pin "NC1") (pinfunction "1_NC1") (pintype "passive"))
      (node (ref "J4") (pin "NC2") (pinfunction "1_NC2") (pintype "passive"))
      (node (ref "J4") (pin "NC3") (pinfunction "1_NC3") (pintype "passive"))
      (node (ref "J4") (pin "NC4") (pinfunction "1_NC4") (pintype "passive"))
      (node (ref "SAR1") (pin "2") (pinfunction "P$2_2") (pintype "bidirectional"))
      (node (ref "SW1") (pin "PE1") (pinfunction "PE_PE1") (pintype "power_in"))
      (node (ref "SW1") (pin "PE2") (pinfunction "PE_PE2") (pintype "power_in"))
      (node (ref "X1") (pin "3") (pinfunction "1_3") (pintype "passive"))
      (node (ref "X1") (pin "6") (pinfunction "1_6") (pintype "passive"))
      (node (ref "X2") (pin "3") (pinfunction "1_3") (pintype "passive"))
      (node (ref "X3") (pin "1") (pinfunction "1_1") (pintype "passive"))
    )
    (net (code "42") (name "PWM_OUT") (class "Default")
      (node (ref "IC2") (pin "6") (pinfunction "PWM_6") (pintype "output"))
      (node (ref "R12") (pin "1") (pinfunction "1_1") (pintype "passive"))
      (node (ref "R14") (pin "2") (pinfunction "2_2") (pintype "passive"))
      (node (ref "X4") (pin "4") (pinfunction "S_4") (pintype "passive"))
      (node (ref "X5") (pin "4") (pinfunction "S_4") (pintype "passive"))
    )
    (net (code "43") (name "PWR_DIRECT") (class "Default")
      (node (ref "R3") (pin "2") (pinfunction "2_2") (pintype "passive"))
      (node (ref "X3") (pin "12") (pinfunction "1_12") (pintype "passive"))
    )
    (net (code "44") (name "PWR_DIR_OUT") (class "Default")
      (node (ref "D3") (pin "A") (pinfunction "A_A") (pintype "passive"))
      (node (ref "K2") (pin "A2") (pinfunction "C1_A2") (pintype "passive"))
      (node (ref "Q1") (pin "C") (pinfunction "C_C") (pintype "passive"))
      (node (ref "Q3") (pin "1") (pinfunction "G_1") (pintype "passive"))
      (node (ref "R7") (pin "2") (pinfunction "2_2") (pintype "passive"))
    )
    (net (code "45") (name "PWR_SSTART") (class "Default")
      (node (ref "R4") (pin "2") (pinfunction "2_2") (pintype "passive"))
      (node (ref "X3") (pin "11") (pinfunction "1_11") (pintype "passive"))
    )
    (net (code "46") (name "SSCL") (class "Default")
      (node (ref "IC2") (pin "15") (pinfunction "SCL_15") (pintype "input"))
      (node (ref "X3") (pin "13") (pinfunction "1_13") (pintype "passive"))
    )
    (net (code "47") (name "SSDA") (class "Default")
      (node (ref "IC2") (pin "14") (pinfunction "SDA_14") (pintype "bidirectional"))
      (node (ref "X3") (pin "14") (pinfunction "1_14") (pintype "passive"))
    )
    (net (code "48") (name "unconnected-(IC2-DXN-Pad2)") (class "Default")
      (node (ref "IC2") (pin "2") (pinfunction "DXN_2") (pintype "input"))
    )
    (net (code "49") (name "unconnected-(IC2-DXP-Pad1)") (class "Default")
      (node (ref "IC2") (pin "1") (pinfunction "DXP_1") (pintype "input"))
    )
    (net (code "50") (name "unconnected-(K1A-S-Pad12A)") (class "Default")
      (node (ref "K1") (pin "12A") (pinfunction "S_12A") (pintype "passive"))
    )
    (net (code "51") (name "unconnected-(K1B-S-Pad12B)") (class "Default")
      (node (ref "K1") (pin "12B") (pinfunction "S_12B") (pintype "passive"))
    )
    (net (code "52") (name "unconnected-(K2A-S-Pad12A)") (class "Default")
      (node (ref "K2") (pin "12A") (pinfunction "S_12A") (pintype "passive"))
    )
    (net (code "53") (name "unconnected-(K2B-S-Pad12B)") (class "Default")
      (node (ref "K2") (pin "12B") (pinfunction "S_12B") (pintype "passive"))
    )
  )
)
